# LM3409HV.net
KiCad netlist of a schematic drawn in EAGLE
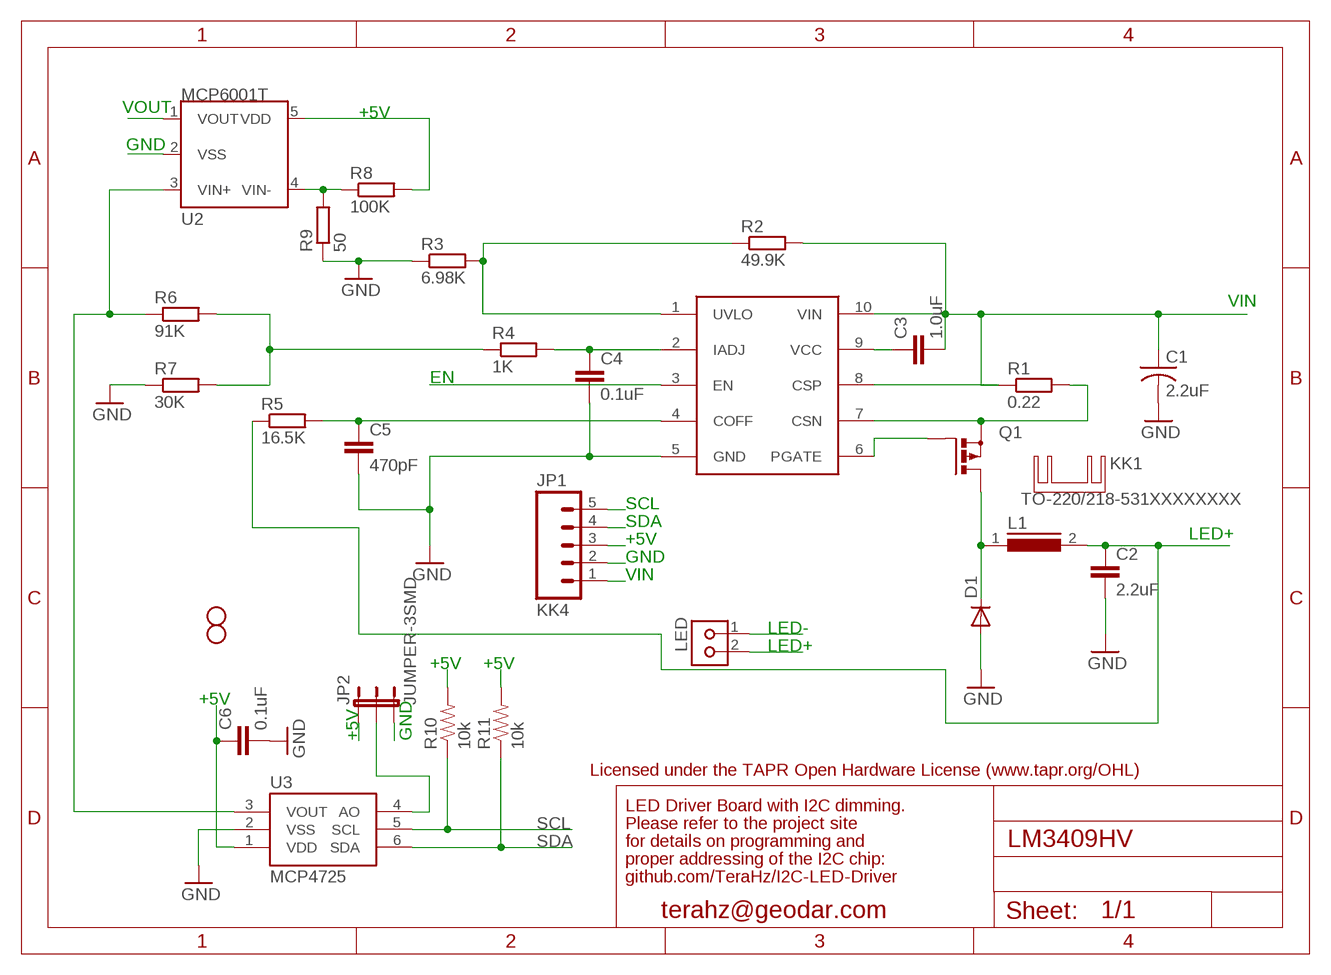
[diagram p0: schematic, sheet 1]

(export (version "E")
  (design (tool "Eeschema 10.0.6"))
  (components
    (comp (ref "C1")
      (value "2.2uF")
      (footprint "eagle-import:C1210")
      (libsource (lib "eagle-import") (part "C-USC1210"))
    )
    (comp (ref "C2")
      (value "2.2uF")
      (footprint "eagle-import:C1210")
      (libsource (lib "eagle-import") (part "C-EUC1210"))
    )
    (comp (ref "C3")
      (value "1.0uF")
      (footprint "eagle-import:0603-CAP")
      (libsource (lib "eagle-import") (part "CAP0603-CAP"))
    )
    (comp (ref "C4")
      (value "0.1uF")
      (footprint "eagle-import:0603-CAP")
      (libsource (lib "eagle-import") (part "CAP0603-CAP"))
    )
    (comp (ref "C5")
      (value "470pF")
      (footprint "eagle-import:0603-CAP")
      (libsource (lib "eagle-import") (part "CAP0603-CAP"))
    )
    (comp (ref "C6")
      (value "0.1uF")
      (footprint "eagle-import:0603-CAP")
      (libsource (lib "eagle-import") (part "CAP0603-CAP"))
    )
    (comp (ref "D1")
      (value "DIODE-SMC")
      (footprint "eagle-import:SMC")
      (libsource (lib "eagle-import") (part "DIODE-SMC"))
    )
    (comp (ref "JP1")
      (value "KK4")
      (footprint "eagle-import:1X05")
      (libsource (lib "eagle-import") (part "M05PTH"))
    )
    (comp (ref "JP2")
      (value "JUMPER-3SMD")
      (footprint "eagle-import:SJ_3")
      (libsource (lib "eagle-import") (part "JUMPER-3SMD"))
    )
    (comp (ref "JP5")
      (value "STAND-OFF")
      (footprint "eagle-import:STAND-OFF")
      (libsource (lib "eagle-import") (part "STAND-OFF"))
    )
    (comp (ref "JP6")
      (value "STAND-OFF")
      (footprint "eagle-import:STAND-OFF")
      (libsource (lib "eagle-import") (part "STAND-OFF"))
    )
    (comp (ref "KK1")
      (value "TO-220/218-531XXXXXXXX")
      (footprint "eagle-import:531XXXXXXXX")
      (libsource (lib "eagle-import") (part "TO-220/218-531XXXXXXXX"))
    )
    (comp (ref "L1")
      (value "DR125")
      (footprint "eagle-import:DR125")
      (libsource (lib "eagle-import") (part "DR125"))
    )
    (comp (ref "LED")
      (value "KK2VRND")
      (footprint "eagle-import:KK-V-2-RND")
      (libsource (lib "eagle-import") (part "KK2VRND"))
    )
    (comp (ref "Q1")
      (value "PMOSFET_PTO220BV")
      (footprint "eagle-import:TO220BV")
      (libsource (lib "eagle-import") (part "PMOSFET_PTO220BV"))
    )
    (comp (ref "R1")
      (value "0.22")
      (footprint "eagle-import:R2512")
      (libsource (lib "eagle-import") (part "R-EU_R2512"))
    )
    (comp (ref "R2")
      (value "49.9K")
      (footprint "eagle-import:R0603")
      (libsource (lib "eagle-import") (part "R-EU_R0603"))
    )
    (comp (ref "R3")
      (value "6.98K")
      (footprint "eagle-import:R0603")
      (libsource (lib "eagle-import") (part "R-EU_R0603"))
    )
    (comp (ref "R4")
      (value "1K")
      (footprint "eagle-import:R0603")
      (libsource (lib "eagle-import") (part "R-EU_R0603"))
    )
    (comp (ref "R5")
      (value "16.5K")
      (footprint "eagle-import:R0603")
      (libsource (lib "eagle-import") (part "R-EU_R0603"))
    )
    (comp (ref "R6")
      (value "91K")
      (footprint "eagle-import:R0603")
      (libsource (lib "eagle-import") (part "R-EU_R0603"))
    )
    (comp (ref "R7")
      (value "30K")
      (footprint "eagle-import:R0603")
      (libsource (lib "eagle-import") (part "R-EU_R0603"))
    )
    (comp (ref "R8")
      (value "100K")
      (footprint "eagle-import:R0603")
      (libsource (lib "eagle-import") (part "R-EU_R0603"))
    )
    (comp (ref "R9")
      (value "50")
      (footprint "eagle-import:R0603")
      (libsource (lib "eagle-import") (part "R-EU_R0603"))
    )
    (comp (ref "R10")
      (value "10k")
      (footprint "eagle-import:0603")
      (libsource (lib "eagle-import") (part "RESISTOR0603"))
    )
    (comp (ref "R11")
      (value "10k")
      (footprint "eagle-import:0603")
      (libsource (lib "eagle-import") (part "RESISTOR0603"))
    )
    (comp (ref "U1")
      (value "LM3409")
      (footprint "eagle-import:MSOP-10-GNDPAD")
      (libsource (lib "eagle-import") (part "LM3409"))
    )
    (comp (ref "U2")
      (value "MCP6001T")
      (footprint "eagle-import:SOT23-5")
      (libsource (lib "eagle-import") (part "MCP6XXX"))
    )
    (comp (ref "U3")
      (value "MCP4725")
      (footprint "eagle-import:SOT23-6")
      (libsource (lib "eagle-import") (part "DAC_MCP4725SOT"))
    )
  )
  (nets
    (net (code "1") (name "/+5V") (class "Default")
      (node (ref "C6") (pin "1") (pinfunction "1_1") (pintype "passive"))
      (node (ref "JP1") (pin "3") (pinfunction "3_3") (pintype "passive"))
      (node (ref "JP2") (pin "1") (pinfunction "1_1") (pintype "passive"))
      (node (ref "R10") (pin "2") (pinfunction "2_2") (pintype "passive"))
      (node (ref "R11") (pin "2") (pinfunction "2_2") (pintype "passive"))
      (node (ref "R8") (pin "2") (pinfunction "2_2") (pintype "passive"))
      (node (ref "U2") (pin "5") (pinfunction "VDD_5") (pintype "bidirectional"))
      (node (ref "U3") (pin "1") (pinfunction "VDD_1") (pintype "bidirectional"))
    )
    (net (code "2") (name "/EN") (class "Default")
      (node (ref "U1") (pin "3") (pinfunction "EN_3") (pintype "bidirectional"))
      (node (ref "U2") (pin "1") (pinfunction "VOUT_1") (pintype "bidirectional"))
    )
    (net (code "3") (name "/LED+") (class "Default")
      (node (ref "C2") (pin "1") (pinfunction "1_1") (pintype "passive"))
      (node (ref "L1") (pin "2") (pinfunction "2_2") (pintype "passive"))
      (node (ref "LED") (pin "2") (pinfunction "2_2") (pintype "bidirectional"))
      (node (ref "R5") (pin "1") (pinfunction "1_1") (pintype "passive"))
    )
    (net (code "4") (name "/SCL") (class "Default")
      (node (ref "JP1") (pin "5") (pinfunction "5_5") (pintype "passive"))
      (node (ref "R10") (pin "1") (pinfunction "1_1") (pintype "passive"))
      (node (ref "U3") (pin "5") (pinfunction "SCL_5") (pintype "bidirectional"))
    )
    (net (code "5") (name "/SDA") (class "Default")
      (node (ref "JP1") (pin "4") (pinfunction "4_4") (pintype "passive"))
      (node (ref "R11") (pin "1") (pinfunction "1_1") (pintype "passive"))
      (node (ref "U3") (pin "6") (pinfunction "SDA_6") (pintype "bidirectional"))
    )
    (net (code "6") (name "/VIN") (class "Default")
      (node (ref "C1") (pin "1") (pinfunction "1_1") (pintype "passive"))
      (node (ref "C3") (pin "2") (pinfunction "2_2") (pintype "passive"))
      (node (ref "JP1") (pin "1") (pinfunction "1_1") (pintype "passive"))
      (node (ref "R1") (pin "1") (pinfunction "1_1") (pintype "passive"))
      (node (ref "R2") (pin "2") (pinfunction "2_2") (pintype "passive"))
      (node (ref "U1") (pin "10") (pinfunction "VIN_10") (pintype "bidirectional"))
      (node (ref "U1") (pin "8") (pinfunction "CSP_8") (pintype "bidirectional"))
    )
    (net (code "7") (name "GND") (class "Default")
      (node (ref "C1") (pin "2") (pinfunction "2_2") (pintype "passive"))
      (node (ref "C2") (pin "2") (pinfunction "2_2") (pintype "passive"))
      (node (ref "C4") (pin "2") (pinfunction "2_2") (pintype "passive"))
      (node (ref "C5") (pin "2") (pinfunction "2_2") (pintype "passive"))
      (node (ref "C6") (pin "2") (pinfunction "2_2") (pintype "passive"))
      (node (ref "D1") (pin "A") (pinfunction "A_A") (pintype "passive"))
      (node (ref "JP1") (pin "2") (pinfunction "2_2") (pintype "passive"))
      (node (ref "JP2") (pin "3") (pinfunction "3_3") (pintype "passive"))
      (node (ref "LED") (pin "1") (pinfunction "1_1") (pintype "bidirectional"))
      (node (ref "R3") (pin "1") (pinfunction "1_1") (pintype "passive"))
      (node (ref "R7") (pin "1") (pinfunction "1_1") (pintype "passive"))
      (node (ref "R9") (pin "1") (pinfunction "1_1") (pintype "passive"))
      (node (ref "U1") (pin "5") (pinfunction "GND_5") (pintype "bidirectional"))
      (node (ref "U2") (pin "2") (pinfunction "VSS_2") (pintype "bidirectional"))
      (node (ref "U3") (pin "2") (pinfunction "VSS_2") (pintype "bidirectional"))
    )
    (net (code "8") (name "Net-(D1-PadC)") (class "Default")
      (node (ref "D1") (pin "C") (pinfunction "C_C") (pintype "passive"))
      (node (ref "L1") (pin "1") (pinfunction "1_1") (pintype "passive"))
      (node (ref "Q1") (pin "D") (pinfunction "D_D") (pintype "passive"))
    )
    (net (code "9") (name "Net-(R4-Pad1)") (class "Default")
      (node (ref "R4") (pin "1") (pinfunction "1_1") (pintype "passive"))
      (node (ref "R6") (pin "2") (pinfunction "2_2") (pintype "passive"))
      (node (ref "R7") (pin "2") (pinfunction "2_2") (pintype "passive"))
    )
    (net (code "10") (name "Net-(U1-COFF)") (class "Default")
      (node (ref "C5") (pin "1") (pinfunction "1_1") (pintype "passive"))
      (node (ref "R5") (pin "2") (pinfunction "2_2") (pintype "passive"))
      (node (ref "U1") (pin "4") (pinfunction "COFF_4") (pintype "bidirectional"))
    )
    (net (code "11") (name "Net-(U1-CSN)") (class "Default")
      (node (ref "Q1") (pin "S") (pinfunction "S_S") (pintype "passive"))
      (node (ref "R1") (pin "2") (pinfunction "2_2") (pintype "passive"))
      (node (ref "U1") (pin "7") (pinfunction "CSN_7") (pintype "bidirectional"))
    )
    (net (code "12") (name "Net-(U1-IADJ)") (class "Default")
      (node (ref "C4") (pin "1") (pinfunction "1_1") (pintype "passive"))
      (node (ref "R4") (pin "2") (pinfunction "2_2") (pintype "passive"))
      (node (ref "U1") (pin "2") (pinfunction "IADJ_2") (pintype "bidirectional"))
    )
    (net (code "13") (name "Net-(U1-PGATE)") (class "Default")
      (node (ref "Q1") (pin "G") (pinfunction "G_G") (pintype "passive"))
      (node (ref "U1") (pin "6") (pinfunction "PGATE_6") (pintype "bidirectional"))
    )
    (net (code "14") (name "Net-(U1-UVLO)") (class "Default")
      (node (ref "R2") (pin "1") (pinfunction "1_1") (pintype "passive"))
      (node (ref "R3") (pin "2") (pinfunction "2_2") (pintype "passive"))
      (node (ref "U1") (pin "1") (pinfunction "UVLO_1") (pintype "bidirectional"))
    )
    (net (code "15") (name "Net-(U1-VCC)") (class "Default")
      (node (ref "C3") (pin "1") (pinfunction "1_1") (pintype "passive"))
      (node (ref "U1") (pin "9") (pinfunction "VCC_9") (pintype "bidirectional"))
    )
    (net (code "16") (name "Net-(U2-VIN+)") (class "Default")
      (node (ref "R6") (pin "1") (pinfunction "1_1") (pintype "passive"))
      (node (ref "U2") (pin "3") (pinfunction "VIN+_3") (pintype "bidirectional"))
      (node (ref "U3") (pin "3") (pinfunction "VOUT_3") (pintype "bidirectional"))
    )
    (net (code "17") (name "Net-(U2-VIN-)") (class "Default")
      (node (ref "R8") (pin "1") (pinfunction "1_1") (pintype "passive"))
      (node (ref "R9") (pin "2") (pinfunction "2_2") (pintype "passive"))
      (node (ref "U2") (pin "4") (pinfunction "VIN-_4") (pintype "bidirectional"))
    )
    (net (code "18") (name "Net-(U3-AO)") (class "Default")
      (node (ref "JP2") (pin "2") (pinfunction "2_2") (pintype "passive"))
      (node (ref "U3") (pin "4") (pinfunction "AO_4") (pintype "bidirectional"))
    )
  )
)
